# Wirelesscharging.net
KiCad netlist of a schematic drawn in Altium Designer
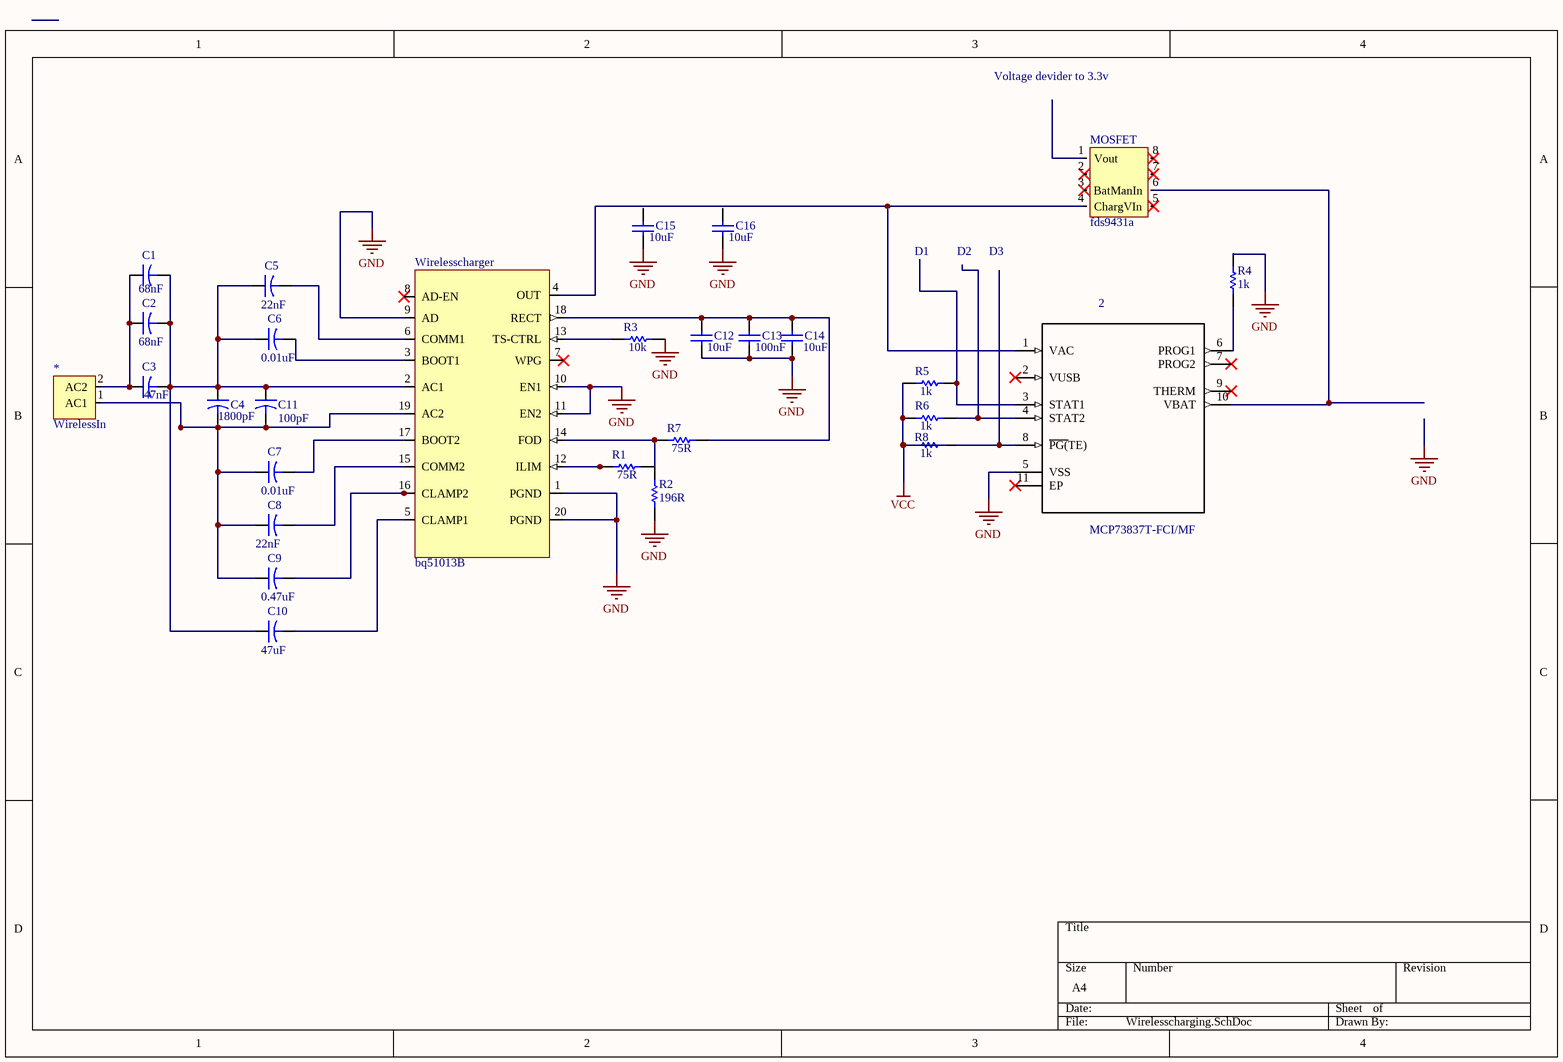
[diagram p0: Wirelesscharging.SchDoc]

(export (version "E")
  (design (tool "Eeschema 10.0.6"))
  (components
    (comp (ref "*")
      (value "WirelessIn")
      (footprint "WirelessIn")
      (libsource (lib "HGCDLibrary") (part "WirelessIn"))
    )
    (comp (ref "2")
      (value "MCP73837T-FCI/MF")
      (footprint "DFN300X300X100-11N")
      (description "MCP73837 Series 6 V Linear Battery Charge Controller Surface Mount - DFN-10")
      (fields (field (name "MF") "Microchip"))
      (libsource (lib "HGCDLibrary") (part "MCP73837T-FCI/MF"))
    )
    (comp (ref "C1")
      (value "68nF")
      (footprint "CAPR5-4X5")
      (description "Capacitor")
      (fields (field (name "Comment") "Cap2") (field (name "PUBLISHER") "Altium Limited"))
      (libsource (lib "Miscellaneous Devices") (part "Cap2"))
    )
    (comp (ref "C2")
      (value "68nF")
      (footprint "CAPR5-4X5")
      (description "Capacitor")
      (fields (field (name "Comment") "Cap2") (field (name "PUBLISHER") "Altium Limited"))
      (libsource (lib "Miscellaneous Devices") (part "Cap2"))
    )
    (comp (ref "C3")
      (value "47nF")
      (footprint "CAPR5-4X5")
      (description "Capacitor")
      (fields (field (name "Comment") "Cap2") (field (name "PUBLISHER") "Altium Limited"))
      (libsource (lib "Miscellaneous Devices") (part "Cap2"))
    )
    (comp (ref "C4")
      (value "1800pF")
      (footprint "CAPR5-4X5")
      (description "Capacitor")
      (fields (field (name "Comment") "Cap2") (field (name "PUBLISHER") "Altium Limited"))
      (libsource (lib "Miscellaneous Devices") (part "Cap2"))
    )
    (comp (ref "C5")
      (value "22nF")
      (footprint "CAPR5-4X5")
      (description "Capacitor")
      (fields (field (name "Comment") "Cap2") (field (name "PUBLISHER") "Altium Limited"))
      (libsource (lib "Miscellaneous Devices") (part "Cap2"))
    )
    (comp (ref "C6")
      (value "0.01uF")
      (footprint "CAPR5-4X5")
      (description "Capacitor")
      (fields (field (name "Comment") "Cap2") (field (name "PUBLISHER") "Altium Limited"))
      (libsource (lib "Miscellaneous Devices") (part "Cap2"))
    )
    (comp (ref "C7")
      (value "0.01uF")
      (footprint "CAPR5-4X5")
      (description "Capacitor")
      (fields (field (name "Comment") "Cap2") (field (name "PUBLISHER") "Altium Limited"))
      (libsource (lib "Miscellaneous Devices") (part "Cap2"))
    )
    (comp (ref "C8")
      (value "22nF")
      (footprint "CAPR5-4X5")
      (description "Capacitor")
      (fields (field (name "Comment") "Cap2") (field (name "PUBLISHER") "Altium Limited"))
      (libsource (lib "Miscellaneous Devices") (part "Cap2"))
    )
    (comp (ref "C9")
      (value "0.47uF")
      (footprint "CAPR5-4X5")
      (description "Capacitor")
      (fields (field (name "Comment") "Cap2") (field (name "PUBLISHER") "Altium Limited"))
      (libsource (lib "Miscellaneous Devices") (part "Cap2"))
    )
    (comp (ref "C10")
      (value "47uF")
      (footprint "CAPR5-4X5")
      (description "Capacitor")
      (fields (field (name "Comment") "Cap2") (field (name "PUBLISHER") "Altium Limited"))
      (libsource (lib "Miscellaneous Devices") (part "Cap2"))
    )
    (comp (ref "C11")
      (value "100pF")
      (footprint "CAPR5-4X5")
      (description "Capacitor")
      (fields (field (name "Comment") "Cap2") (field (name "PUBLISHER") "Altium Limited"))
      (libsource (lib "Miscellaneous Devices") (part "Cap2"))
    )
    (comp (ref "C12")
      (value "10uF")
      (footprint "RAD-0.3")
      (description "Capacitor")
      (fields (field (name "Comment") "Cap") (field (name "PUBLISHER") "Altium Limited"))
      (libsource (lib "Miscellaneous Devices") (part "Cap"))
    )
    (comp (ref "C13")
      (value "100nF")
      (footprint "RAD-0.3")
      (description "Capacitor")
      (fields (field (name "Comment") "Cap") (field (name "PUBLISHER") "Altium Limited"))
      (libsource (lib "Miscellaneous Devices") (part "Cap"))
    )
    (comp (ref "C14")
      (value "10uF")
      (footprint "RAD-0.3")
      (description "Capacitor")
      (fields (field (name "Comment") "Cap") (field (name "PUBLISHER") "Altium Limited"))
      (libsource (lib "Miscellaneous Devices") (part "Cap"))
    )
    (comp (ref "C15")
      (value "10uF")
      (footprint "RAD-0.3")
      (description "Capacitor")
      (fields (field (name "Comment") "Cap") (field (name "PUBLISHER") "Altium Limited"))
      (libsource (lib "Miscellaneous Devices") (part "Cap"))
    )
    (comp (ref "C16")
      (value "10uF")
      (footprint "RAD-0.3")
      (description "Capacitor")
      (fields (field (name "Comment") "Cap") (field (name "PUBLISHER") "Altium Limited"))
      (libsource (lib "Miscellaneous Devices") (part "Cap"))
    )
    (comp (ref "MOSFET")
      (value "fds9431a")
      (footprint "SOIC127P600X175-8N")
      (libsource (lib "ExtraComp") (part "fds9431a"))
    )
    (comp (ref "R1")
      (value "75R")
      (footprint "AXIAL-0.3")
      (description "Resistor")
      (fields (field (name "Comment") "Res1") (field (name "PUBLISHER") "Altium Limited"))
      (libsource (lib "Miscellaneous Devices") (part "Res1"))
    )
    (comp (ref "R2")
      (value "196R")
      (footprint "AXIAL-0.3")
      (description "Resistor")
      (fields (field (name "Comment") "Res1") (field (name "PUBLISHER") "Altium Limited"))
      (libsource (lib "Miscellaneous Devices") (part "Res1"))
    )
    (comp (ref "R3")
      (value "10k")
      (footprint "AXIAL-0.3")
      (description "Resistor")
      (fields (field (name "Comment") "Res1") (field (name "PUBLISHER") "Altium Limited"))
      (libsource (lib "Miscellaneous Devices") (part "Res1"))
    )
    (comp (ref "R4")
      (value "1k")
      (footprint "AXIAL-0.3")
      (description "Resistor")
      (fields (field (name "Comment") "Res1") (field (name "PUBLISHER") "Altium Limited"))
      (libsource (lib "Miscellaneous Devices") (part "Res1"))
    )
    (comp (ref "R5")
      (value "1k")
      (footprint "AXIAL-0.3")
      (description "Resistor")
      (fields (field (name "Comment") "Res1") (field (name "PUBLISHER") "Altium Limited"))
      (libsource (lib "Miscellaneous Devices") (part "Res1"))
    )
    (comp (ref "R6")
      (value "1k")
      (footprint "AXIAL-0.3")
      (description "Resistor")
      (fields (field (name "Comment") "Res1") (field (name "PUBLISHER") "Altium Limited"))
      (libsource (lib "Miscellaneous Devices") (part "Res1"))
    )
    (comp (ref "R7")
      (value "75R")
      (footprint "AXIAL-0.3")
      (description "Resistor")
      (fields (field (name "Comment") "Res1") (field (name "PUBLISHER") "Altium Limited"))
      (libsource (lib "Miscellaneous Devices") (part "Res1"))
    )
    (comp (ref "R8")
      (value "1k")
      (footprint "AXIAL-0.3")
      (description "Resistor")
      (fields (field (name "Comment") "Res1") (field (name "PUBLISHER") "Altium Limited"))
      (libsource (lib "Miscellaneous Devices") (part "Res1"))
    )
    (comp (ref "Wirelesscharger")
      (value "bq51013B")
      (footprint "CONTROLLER_MSP430FR2522IRHLT")
      (libsource (lib "HGCDLibrary") (part "bq51013B"))
    )
  )
  (nets
    (net (code "1") (name "GND") (class "Default")
      (node (ref "2") (pin "5") (pinfunction "VSS_5") (pintype "power_in"))
      (node (ref "C12") (pin "1") (pinfunction "1_1") (pintype "passive"))
      (node (ref "C13") (pin "1") (pinfunction "1_1") (pintype "passive"))
      (node (ref "C14") (pin "1") (pinfunction "1_1") (pintype "passive"))
      (node (ref "C15") (pin "1") (pinfunction "1_1") (pintype "passive"))
      (node (ref "C16") (pin "1") (pinfunction "1_1") (pintype "passive"))
      (node (ref "R2") (pin "1") (pinfunction "1_1") (pintype "passive"))
      (node (ref "R3") (pin "2") (pinfunction "2_2") (pintype "passive"))
      (node (ref "R4") (pin "2") (pinfunction "2_2") (pintype "passive"))
      (node (ref "Wirelesscharger") (pin "1") (pinfunction "PGND_1") (pintype "power_in"))
      (node (ref "Wirelesscharger") (pin "10") (pinfunction "EN1_10") (pintype "input"))
      (node (ref "Wirelesscharger") (pin "11") (pinfunction "EN2_11") (pintype "input"))
      (node (ref "Wirelesscharger") (pin "20") (pinfunction "PGND_20") (pintype "power_in"))
      (node (ref "Wirelesscharger") (pin "9") (pinfunction "AD_9") (pintype "power_in"))
    )
    (net (code "2") (name "Net-(*-AC1)") (class "Default")
      (node (ref "*") (pin "1") (pinfunction "AC1_1") (pintype "input"))
      (node (ref "C11") (pin "2") (pinfunction "2_2") (pintype "passive"))
      (node (ref "C4") (pin "2") (pinfunction "2_2") (pintype "passive"))
      (node (ref "C7") (pin "1") (pinfunction "1_1") (pintype "passive"))
      (node (ref "C8") (pin "1") (pinfunction "1_1") (pintype "passive"))
      (node (ref "C9") (pin "1") (pinfunction "1_1") (pintype "passive"))
      (node (ref "Wirelesscharger") (pin "19") (pinfunction "AC2_19") (pintype "input"))
    )
    (net (code "3") (name "Net-(*-AC2)") (class "Default")
      (node (ref "*") (pin "2") (pinfunction "AC2_2") (pintype "input"))
      (node (ref "C1") (pin "1") (pinfunction "1_1") (pintype "passive"))
      (node (ref "C2") (pin "1") (pinfunction "1_1") (pintype "passive"))
      (node (ref "C3") (pin "1") (pinfunction "1_1") (pintype "passive"))
    )
    (net (code "4") (name "Net-(2-PROG1)") (class "Default")
      (node (ref "2") (pin "6") (pinfunction "PROG1_6") (pintype "output"))
      (node (ref "R4") (pin "1") (pinfunction "1_1") (pintype "passive"))
    )
    (net (code "5") (name "Net-(2-STAT1)") (class "Default")
      (node (ref "2") (pin "3") (pinfunction "STAT1_3") (pintype "input"))
      (node (ref "R5") (pin "2") (pinfunction "2_2") (pintype "passive"))
    )
    (net (code "6") (name "Net-(2-STAT2)") (class "Default")
      (node (ref "2") (pin "4") (pinfunction "STAT2_4") (pintype "input"))
      (node (ref "R6") (pin "2") (pinfunction "2_2") (pintype "passive"))
    )
    (net (code "7") (name "Net-(2-VAC)") (class "Default")
      (node (ref "2") (pin "1") (pinfunction "VAC_1") (pintype "input"))
      (node (ref "MOSFET") (pin "4") (pinfunction "ChargVIn_4") (pintype "input"))
      (node (ref "Wirelesscharger") (pin "4") (pinfunction "OUT_4") (pintype "power_in"))
    )
    (net (code "8") (name "Net-(2-VBAT)") (class "Default")
      (node (ref "2") (pin "10") (pinfunction "VBAT_10") (pintype "output"))
      (node (ref "MOSFET") (pin "6") (pinfunction "BatManIn_6") (pintype "input"))
    )
    (net (code "9") (name "Net-(2-~{PG(}TE))") (class "Default")
      (node (ref "2") (pin "8") (pinfunction "~{PG(}TE)_8") (pintype "input"))
      (node (ref "R8") (pin "2") (pinfunction "2_2") (pintype "passive"))
    )
    (net (code "10") (name "Net-(Wirelesscharger-AC1)") (class "Default")
      (node (ref "C1") (pin "2") (pinfunction "2_2") (pintype "passive"))
      (node (ref "C10") (pin "1") (pinfunction "1_1") (pintype "passive"))
      (node (ref "C11") (pin "1") (pinfunction "1_1") (pintype "passive"))
      (node (ref "C2") (pin "2") (pinfunction "2_2") (pintype "passive"))
      (node (ref "C3") (pin "2") (pinfunction "2_2") (pintype "passive"))
      (node (ref "C4") (pin "1") (pinfunction "1_1") (pintype "passive"))
      (node (ref "C5") (pin "1") (pinfunction "1_1") (pintype "passive"))
      (node (ref "C6") (pin "1") (pinfunction "1_1") (pintype "passive"))
      (node (ref "Wirelesscharger") (pin "2") (pinfunction "AC1_2") (pintype "input"))
    )
    (net (code "11") (name "Net-(Wirelesscharger-BOOT1)") (class "Default")
      (node (ref "C6") (pin "2") (pinfunction "2_2") (pintype "passive"))
      (node (ref "Wirelesscharger") (pin "3") (pinfunction "BOOT1_3") (pintype "output"))
    )
    (net (code "12") (name "Net-(Wirelesscharger-BOOT2)") (class "Default")
      (node (ref "C7") (pin "2") (pinfunction "2_2") (pintype "passive"))
      (node (ref "Wirelesscharger") (pin "17") (pinfunction "BOOT2_17") (pintype "output"))
    )
    (net (code "13") (name "Net-(Wirelesscharger-CLAMP1)") (class "Default")
      (node (ref "C10") (pin "2") (pinfunction "2_2") (pintype "passive"))
      (node (ref "Wirelesscharger") (pin "5") (pinfunction "CLAMP1_5") (pintype "output"))
    )
    (net (code "14") (name "Net-(Wirelesscharger-CLAMP2)") (class "Default")
      (node (ref "C9") (pin "2") (pinfunction "2_2") (pintype "passive"))
      (node (ref "Wirelesscharger") (pin "16") (pinfunction "CLAMP2_16") (pintype "output"))
    )
    (net (code "15") (name "Net-(Wirelesscharger-COMM1)") (class "Default")
      (node (ref "C5") (pin "2") (pinfunction "2_2") (pintype "passive"))
      (node (ref "Wirelesscharger") (pin "6") (pinfunction "COMM1_6") (pintype "output"))
    )
    (net (code "16") (name "Net-(Wirelesscharger-COMM2)") (class "Default")
      (node (ref "C8") (pin "2") (pinfunction "2_2") (pintype "passive"))
      (node (ref "Wirelesscharger") (pin "15") (pinfunction "COMM2_15") (pintype "output"))
    )
    (net (code "17") (name "Net-(Wirelesscharger-FOD)") (class "Default")
      (node (ref "R2") (pin "2") (pinfunction "2_2") (pintype "passive"))
      (node (ref "R7") (pin "1") (pinfunction "1_1") (pintype "passive"))
      (node (ref "Wirelesscharger") (pin "14") (pinfunction "FOD_14") (pintype "input"))
    )
    (net (code "18") (name "Net-(Wirelesscharger-ILIM)") (class "Default")
      (node (ref "R1") (pin "1") (pinfunction "1_1") (pintype "passive"))
      (node (ref "Wirelesscharger") (pin "12") (pinfunction "ILIM_12") (pintype "input"))
    )
    (net (code "19") (name "Net-(Wirelesscharger-RECT)") (class "Default")
      (node (ref "C12") (pin "2") (pinfunction "2_2") (pintype "passive"))
      (node (ref "C13") (pin "2") (pinfunction "2_2") (pintype "passive"))
      (node (ref "C14") (pin "2") (pinfunction "2_2") (pintype "passive"))
      (node (ref "R7") (pin "2") (pinfunction "2_2") (pintype "passive"))
      (node (ref "Wirelesscharger") (pin "18") (pinfunction "RECT_18") (pintype "output"))
    )
    (net (code "20") (name "Net-(Wirelesscharger-TS-CTRL)") (class "Default")
      (node (ref "R3") (pin "1") (pinfunction "1_1") (pintype "passive"))
      (node (ref "Wirelesscharger") (pin "13") (pinfunction "TS-CTRL_13") (pintype "input"))
    )
    (net (code "21") (name "VCC") (class "Default")
      (node (ref "R5") (pin "1") (pinfunction "1_1") (pintype "passive"))
      (node (ref "R6") (pin "1") (pinfunction "1_1") (pintype "passive"))
      (node (ref "R8") (pin "1") (pinfunction "1_1") (pintype "passive"))
    )
    (net (code "22") (name "unconnected-(2-EP-Pad11)") (class "Default")
      (node (ref "2") (pin "11") (pinfunction "EP_11") (pintype "passive+no_connect"))
    )
    (net (code "23") (name "unconnected-(2-PROG2-Pad7)") (class "Default")
      (node (ref "2") (pin "7") (pinfunction "PROG2_7") (pintype "output+no_connect"))
    )
    (net (code "24") (name "unconnected-(2-THERM-Pad9)") (class "Default")
      (node (ref "2") (pin "9") (pinfunction "THERM_9") (pintype "output+no_connect"))
    )
    (net (code "25") (name "unconnected-(2-VUSB-Pad2)") (class "Default")
      (node (ref "2") (pin "2") (pinfunction "VUSB_2") (pintype "input+no_connect"))
    )
    (net (code "26") (name "unconnected-(C15-Pad2)") (class "Default")
      (node (ref "C15") (pin "2") (pinfunction "2_2") (pintype "passive"))
    )
    (net (code "27") (name "unconnected-(C16-Pad2)") (class "Default")
      (node (ref "C16") (pin "2") (pinfunction "2_2") (pintype "passive"))
    )
    (net (code "28") (name "unconnected-(MOSFET-22-Pad2)") (class "Default")
      (node (ref "MOSFET") (pin "2") (pinfunction "22_2") (pintype "passive+no_connect"))
    )
    (net (code "29") (name "unconnected-(MOSFET-22-Pad5)") (class "Default")
      (node (ref "MOSFET") (pin "5") (pinfunction "22_5") (pintype "passive+no_connect"))
    )
    (net (code "30") (name "unconnected-(MOSFET-22-Pad7)") (class "Default")
      (node (ref "MOSFET") (pin "7") (pinfunction "22_7") (pintype "passive+no_connect"))
    )
    (net (code "31") (name "unconnected-(MOSFET-22-Pad8)") (class "Default")
      (node (ref "MOSFET") (pin "8") (pinfunction "22_8") (pintype "passive+no_connect"))
    )
    (net (code "32") (name "unconnected-(MOSFET-23-Pad3)") (class "Default")
      (node (ref "MOSFET") (pin "3") (pinfunction "23_3") (pintype "passive+no_connect"))
    )
    (net (code "33") (name "unconnected-(MOSFET-Vout-Pad1)") (class "Default")
      (node (ref "MOSFET") (pin "1") (pinfunction "Vout_1") (pintype "output"))
    )
    (net (code "34") (name "unconnected-(R1-Pad2)") (class "Default")
      (node (ref "R1") (pin "2") (pinfunction "2_2") (pintype "passive"))
    )
    (net (code "35") (name "unconnected-(Wirelesscharger-AD-EN-Pad8)") (class "Default")
      (node (ref "Wirelesscharger") (pin "8") (pinfunction "AD-EN_8") (pintype "power_in+no_connect"))
    )
    (net (code "36") (name "unconnected-(Wirelesscharger-WPG-Pad7)") (class "Default")
      (node (ref "Wirelesscharger") (pin "7") (pinfunction "WPG_7") (pintype "power_in+no_connect"))
    )
  )
)
